# RasPi-BplusHAT.net
KiCad netlist of a schematic drawn in EAGLE
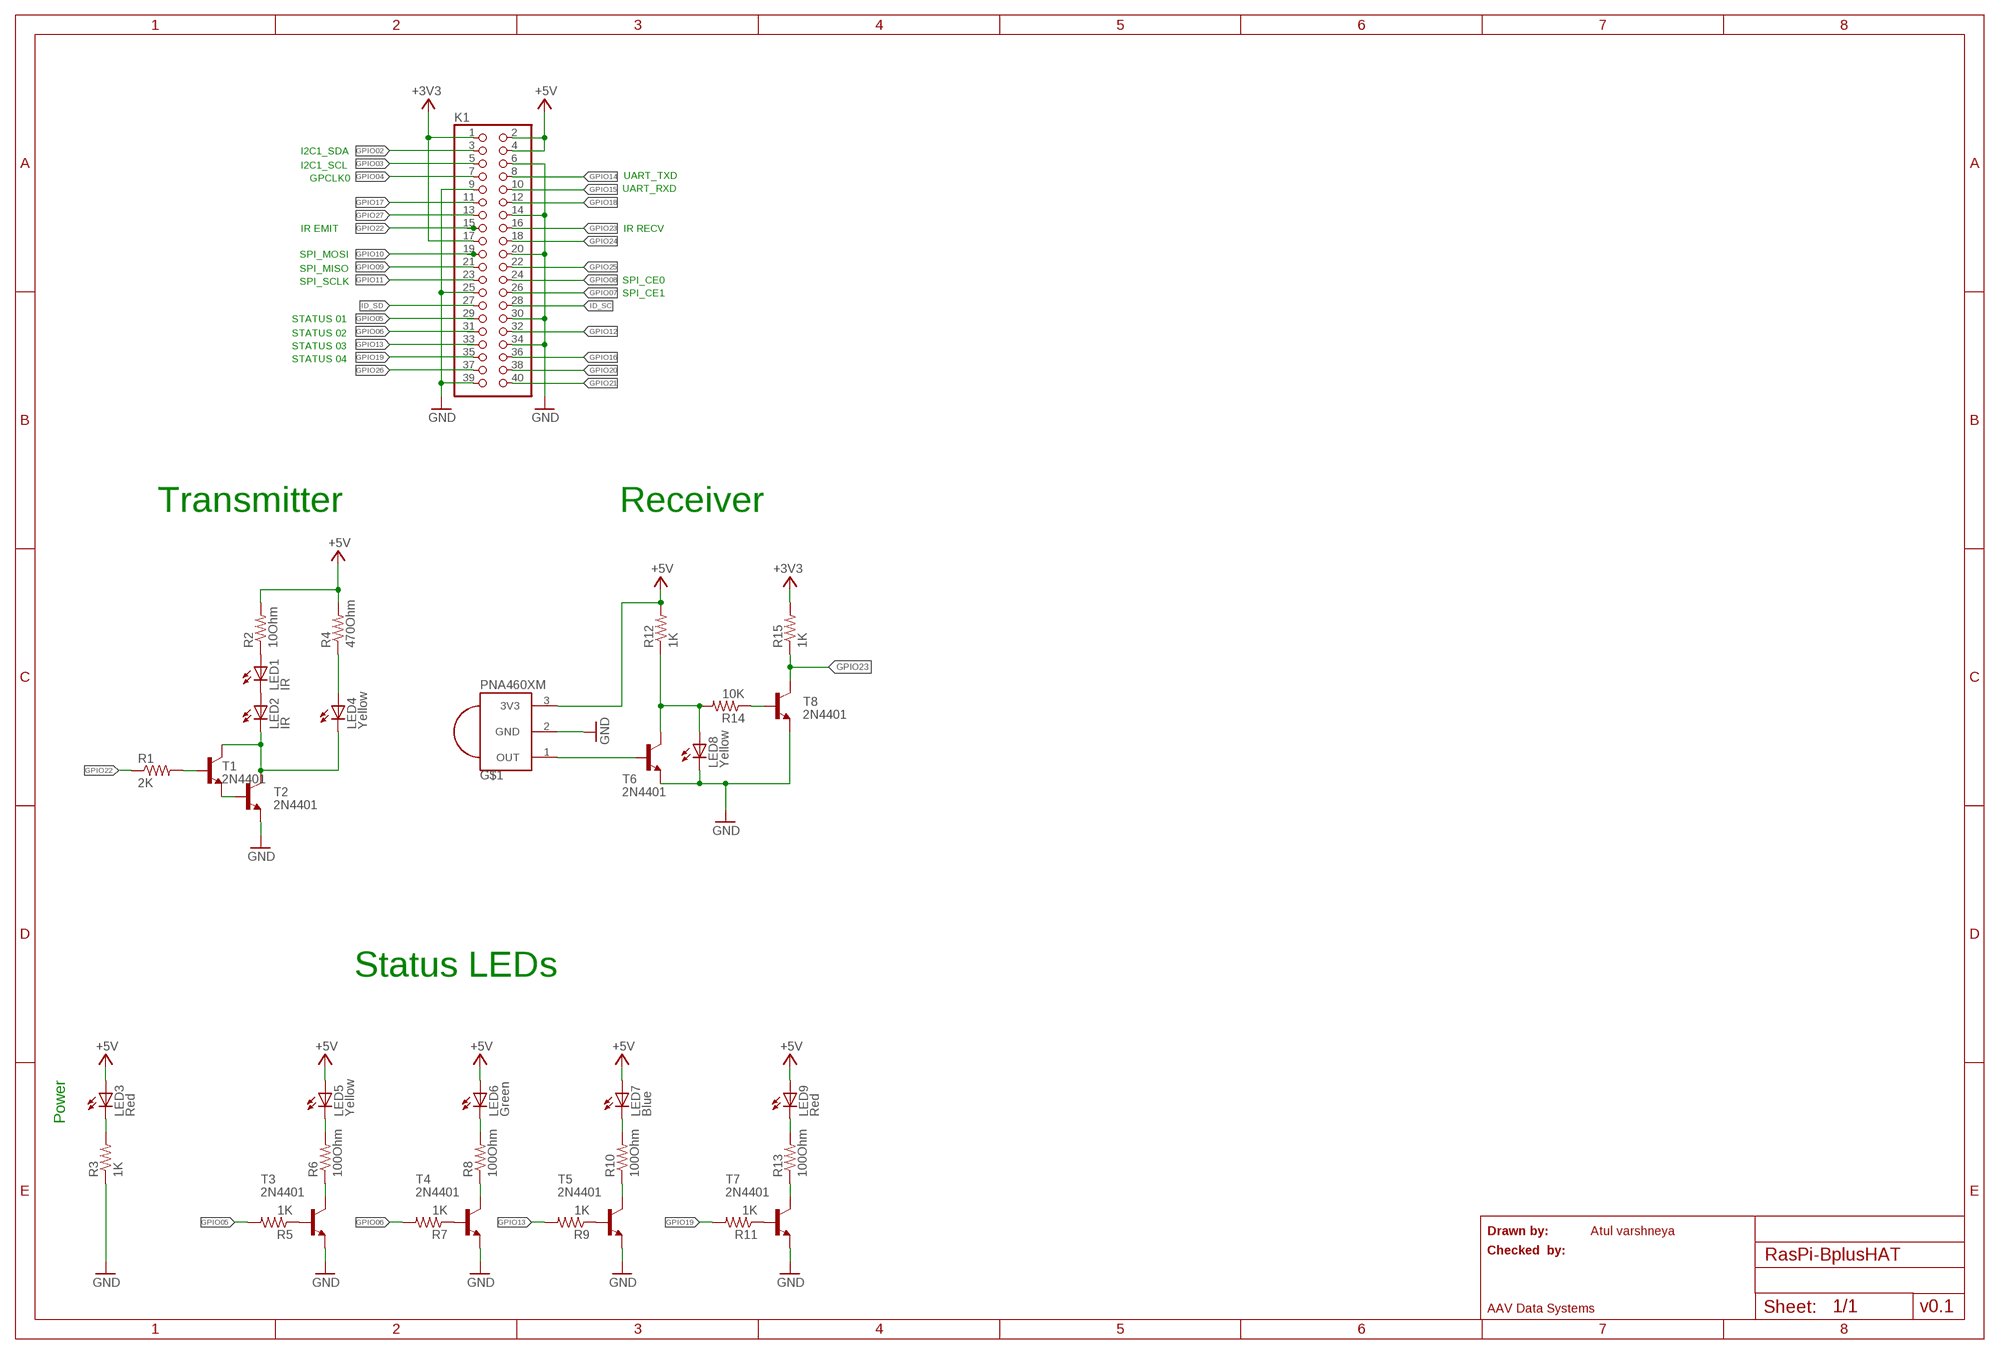
[diagram p0: schematic, sheet 1]

(export (version "E")
  (design (tool "Eeschema 10.0.6"))
  (components
    (comp (ref "G$1")
      (value "PNA460XM")
      (footprint "eagle-import:PNA460XM")
      (fields (field (name "MPN") "TSDP34138"))
      (libsource (lib "eagle-import") (part "PNA460XM"))
    )
    (comp (ref "K1")
      (value "PINHD-2X20")
      (footprint "eagle-import:2X20")
      (libsource (lib "eagle-import") (part "PINHD-2X20"))
    )
    (comp (ref "LED1")
      (value "IR")
      (footprint "eagle-import:MICRO-SIDELED")
      (fields (field (name "MPN") "VSMB10940X01"))
      (libsource (lib "eagle-import") (part "led_LEDMICRO-SIDELED"))
    )
    (comp (ref "LED2")
      (value "IR")
      (footprint "eagle-import:MICRO-SIDELED")
      (fields (field (name "MPN") "VSMB10940X01"))
      (libsource (lib "eagle-import") (part "led_LEDMICRO-SIDELED"))
    )
    (comp (ref "LED3")
      (value "Red")
      (footprint "eagle-import:CHIPLED_0805")
      (fields (field (name "MPN") "150080RS75000"))
      (libsource (lib "eagle-import") (part "LEDCHIPLED_0805"))
    )
    (comp (ref "LED4")
      (value "Yellow")
      (footprint "eagle-import:CHIPLED_0805")
      (fields (field (name "MPN") "150080YS75000"))
      (libsource (lib "eagle-import") (part "LEDCHIPLED_0805"))
    )
    (comp (ref "LED5")
      (value "Yellow")
      (footprint "eagle-import:CHIPLED_0805")
      (fields (field (name "MPN") "150080YS75000"))
      (libsource (lib "eagle-import") (part "LEDCHIPLED_0805"))
    )
    (comp (ref "LED6")
      (value "Green")
      (footprint "eagle-import:CHIPLED_0805")
      (fields (field (name "MPN") "150080GS75000"))
      (libsource (lib "eagle-import") (part "LEDCHIPLED_0805"))
    )
    (comp (ref "LED7")
      (value "Blue")
      (footprint "eagle-import:CHIPLED_0805")
      (fields (field (name "MPN") "150080BS75000"))
      (libsource (lib "eagle-import") (part "LEDCHIPLED_0805"))
    )
    (comp (ref "LED8")
      (value "Yellow")
      (footprint "eagle-import:CHIPLED_0805")
      (fields (field (name "MPN") "150080YS75000"))
      (libsource (lib "eagle-import") (part "LEDCHIPLED_0805"))
    )
    (comp (ref "LED9")
      (value "Red")
      (footprint "eagle-import:CHIPLED_0805")
      (fields (field (name "MPN") "150080RS75000"))
      (libsource (lib "eagle-import") (part "LEDCHIPLED_0805"))
    )
    (comp (ref "R1")
      (value "2K")
      (footprint "eagle-import:R0805")
      (fields (field (name "MPN") "CRCW08052K00JNEA"))
      (libsource (lib "eagle-import") (part "R-US_R0805"))
    )
    (comp (ref "R2")
      (value "10Ohm")
      (footprint "eagle-import:R0805")
      (fields (field (name "MF") "OUTSOURCE ITEM") (field (name "MPN") "RP2012S-100-F"))
      (libsource (lib "eagle-import") (part "R-US_R0805"))
    )
    (comp (ref "R3")
      (value "1K")
      (footprint "eagle-import:R0805")
      (fields (field (name "MF") "VISHAY/DALE") (field (name "MPN") "CRCW08051K00JNEA"))
      (libsource (lib "eagle-import") (part "rcl_R-US_R0805"))
    )
    (comp (ref "R4")
      (value "470Ohm")
      (footprint "eagle-import:R0805")
      (fields (field (name "MPN") "CRCW0805470RJNEA"))
      (libsource (lib "eagle-import") (part "R-US_R0805"))
    )
    (comp (ref "R5")
      (value "1K")
      (footprint "eagle-import:R0805")
      (fields (field (name "MF") "VISHAY/DALE") (field (name "MPN") "CRCW08051K00JNEA"))
      (libsource (lib "eagle-import") (part "rcl_R-US_R0805"))
    )
    (comp (ref "R6")
      (value "100Ohm")
      (footprint "eagle-import:R0805")
      (fields (field (name "MPN") "CRCW0805100RJNTA"))
      (libsource (lib "eagle-import") (part "rcl_R-US_R0805"))
    )
    (comp (ref "R7")
      (value "1K")
      (footprint "eagle-import:R0805")
      (fields (field (name "MF") "VISHAY/DALE") (field (name "MPN") "CRCW08051K00JNEA"))
      (libsource (lib "eagle-import") (part "rcl_R-US_R0805"))
    )
    (comp (ref "R8")
      (value "100Ohm")
      (footprint "eagle-import:R0805")
      (fields (field (name "MPN") "CRCW0805100RJNTA"))
      (libsource (lib "eagle-import") (part "rcl_R-US_R0805"))
    )
    (comp (ref "R9")
      (value "1K")
      (footprint "eagle-import:R0805")
      (fields (field (name "MF") "VISHAY/DALE") (field (name "MPN") "CRCW08051K00JNEA"))
      (libsource (lib "eagle-import") (part "rcl_R-US_R0805"))
    )
    (comp (ref "R10")
      (value "100Ohm")
      (footprint "eagle-import:R0805")
      (fields (field (name "MPN") "CRCW0805100RJNTA"))
      (libsource (lib "eagle-import") (part "rcl_R-US_R0805"))
    )
    (comp (ref "R11")
      (value "1K")
      (footprint "eagle-import:R0805")
      (fields (field (name "MF") "VISHAY/DALE") (field (name "MPN") "CRCW08051K00JNEA"))
      (libsource (lib "eagle-import") (part "rcl_R-US_R0805"))
    )
    (comp (ref "R12")
      (value "1K")
      (footprint "eagle-import:R0805")
      (fields (field (name "MF") "VISHAY/DALE") (field (name "MPN") "CRCW08051K00JNEA"))
      (libsource (lib "eagle-import") (part "rcl_R-US_R0805"))
    )
    (comp (ref "R13")
      (value "100Ohm")
      (footprint "eagle-import:R0805")
      (fields (field (name "MPN") "CRCW0805100RJNTA"))
      (libsource (lib "eagle-import") (part "rcl_R-US_R0805"))
    )
    (comp (ref "R14")
      (value "10K")
      (footprint "eagle-import:R0805")
      (fields (field (name "MF") "VISHAY/DALE") (field (name "MPN") "CRCW080510K0JNEB"))
      (libsource (lib "eagle-import") (part "rcl_R-US_R0805"))
    )
    (comp (ref "R15")
      (value "1K")
      (footprint "eagle-import:R0805")
      (fields (field (name "MF") "VISHAY/DALE") (field (name "MPN") "CRCW08051K00JNEA"))
      (libsource (lib "eagle-import") (part "rcl_R-US_R0805"))
    )
    (comp (ref "T1")
      (value "2N4401")
      (footprint "eagle-import:SOT23-BEC")
      (fields (field (name "MPN") "MMBT4401-TP"))
      (libsource (lib "eagle-import") (part "transistor-neu-to92_-NPN-SOT23-BECMMBT4401LT1"))
    )
    (comp (ref "T2")
      (value "2N4401")
      (footprint "eagle-import:SOT23-BEC")
      (fields (field (name "MPN") "MMBT4401-TP"))
      (libsource (lib "eagle-import") (part "transistor-neu-to92_-NPN-SOT23-BECMMBT4401LT1"))
    )
    (comp (ref "T3")
      (value "2N4401")
      (footprint "eagle-import:SOT23-BEC")
      (fields (field (name "MPN") "MMBT4401-TP"))
      (libsource (lib "eagle-import") (part "-NPN-SOT23-BECMMBT4401LT1"))
    )
    (comp (ref "T4")
      (value "2N4401")
      (footprint "eagle-import:SOT23-BEC")
      (fields (field (name "MPN") "MMBT4401-TP"))
      (libsource (lib "eagle-import") (part "-NPN-SOT23-BECMMBT4401LT1"))
    )
    (comp (ref "T5")
      (value "2N4401")
      (footprint "eagle-import:SOT23-BEC")
      (fields (field (name "MPN") "MMBT4401-TP"))
      (libsource (lib "eagle-import") (part "-NPN-SOT23-BECMMBT4401LT1"))
    )
    (comp (ref "T6")
      (value "2N4401")
      (footprint "eagle-import:SOT23-BEC")
      (fields (field (name "MPN") "MMBT4401-TP"))
      (libsource (lib "eagle-import") (part "-NPN-SOT23-BECMMBT4401LT1"))
    )
    (comp (ref "T7")
      (value "2N4401")
      (footprint "eagle-import:SOT23-BEC")
      (fields (field (name "MPN") "MMBT4401-TP"))
      (libsource (lib "eagle-import") (part "-NPN-SOT23-BECMMBT4401LT1"))
    )
    (comp (ref "T8")
      (value "2N4401")
      (footprint "eagle-import:SOT23-BEC")
      (fields (field (name "MPN") "MMBT4401-TP"))
      (libsource (lib "eagle-import") (part "-NPN-SOT23-BECMMBT4401LT1"))
    )
  )
  (nets
    (net (code "1") (name "+3V3") (class "Default")
      (node (ref "K1") (pin "1") (pinfunction "1_1") (pintype "passive"))
      (node (ref "K1") (pin "17") (pinfunction "17_17") (pintype "passive"))
      (node (ref "R15") (pin "2") (pinfunction "2_2") (pintype "passive"))
    )
    (net (code "2") (name "+5V") (class "Default")
      (node (ref "G$1") (pin "3") (pinfunction "3V3_3") (pintype "power_in"))
      (node (ref "K1") (pin "2") (pinfunction "2_2") (pintype "passive"))
      (node (ref "K1") (pin "4") (pinfunction "4_4") (pintype "passive"))
      (node (ref "LED3") (pin "A") (pinfunction "A_A") (pintype "passive"))
      (node (ref "LED5") (pin "A") (pinfunction "A_A") (pintype "passive"))
      (node (ref "LED6") (pin "A") (pinfunction "A_A") (pintype "passive"))
      (node (ref "LED7") (pin "A") (pinfunction "A_A") (pintype "passive"))
      (node (ref "LED9") (pin "A") (pinfunction "A_A") (pintype "passive"))
      (node (ref "R12") (pin "2") (pinfunction "2_2") (pintype "passive"))
      (node (ref "R2") (pin "2") (pinfunction "2_2") (pintype "passive"))
      (node (ref "R4") (pin "2") (pinfunction "2_2") (pintype "passive"))
    )
    (net (code "3") (name "GND") (class "Default")
      (node (ref "G$1") (pin "2") (pinfunction "GND_2") (pintype "power_in"))
      (node (ref "K1") (pin "14") (pinfunction "14_14") (pintype "passive"))
      (node (ref "K1") (pin "20") (pinfunction "20_20") (pintype "passive"))
      (node (ref "K1") (pin "25") (pinfunction "25_25") (pintype "passive"))
      (node (ref "K1") (pin "30") (pinfunction "30_30") (pintype "passive"))
      (node (ref "K1") (pin "34") (pinfunction "34_34") (pintype "passive"))
      (node (ref "K1") (pin "39") (pinfunction "39_39") (pintype "passive"))
      (node (ref "K1") (pin "6") (pinfunction "6_6") (pintype "passive"))
      (node (ref "K1") (pin "9") (pinfunction "9_9") (pintype "passive"))
      (node (ref "LED8") (pin "C") (pinfunction "C_C") (pintype "passive"))
      (node (ref "R3") (pin "1") (pinfunction "1_1") (pintype "passive"))
      (node (ref "T2") (pin "E") (pinfunction "E_E") (pintype "passive"))
      (node (ref "T3") (pin "E") (pinfunction "E_E") (pintype "passive"))
      (node (ref "T4") (pin "E") (pinfunction "E_E") (pintype "passive"))
      (node (ref "T5") (pin "E") (pinfunction "E_E") (pintype "passive"))
      (node (ref "T6") (pin "E") (pinfunction "E_E") (pintype "passive"))
      (node (ref "T7") (pin "E") (pinfunction "E_E") (pintype "passive"))
      (node (ref "T8") (pin "E") (pinfunction "E_E") (pintype "passive"))
    )
    (net (code "4") (name "GPIO02") (class "Default")
      (node (ref "K1") (pin "3") (pinfunction "3_3") (pintype "passive"))
    )
    (net (code "5") (name "GPIO03") (class "Default")
      (node (ref "K1") (pin "5") (pinfunction "5_5") (pintype "passive"))
    )
    (net (code "6") (name "GPIO04") (class "Default")
      (node (ref "K1") (pin "7") (pinfunction "7_7") (pintype "passive"))
    )
    (net (code "7") (name "GPIO05") (class "Default")
      (node (ref "K1") (pin "29") (pinfunction "29_29") (pintype "passive"))
      (node (ref "R5") (pin "2") (pinfunction "2_2") (pintype "passive"))
    )
    (net (code "8") (name "GPIO06") (class "Default")
      (node (ref "K1") (pin "31") (pinfunction "31_31") (pintype "passive"))
      (node (ref "R7") (pin "2") (pinfunction "2_2") (pintype "passive"))
    )
    (net (code "9") (name "GPIO07") (class "Default")
      (node (ref "K1") (pin "26") (pinfunction "26_26") (pintype "passive"))
    )
    (net (code "10") (name "GPIO08") (class "Default")
      (node (ref "K1") (pin "24") (pinfunction "24_24") (pintype "passive"))
    )
    (net (code "11") (name "GPIO09") (class "Default")
      (node (ref "K1") (pin "21") (pinfunction "21_21") (pintype "passive"))
    )
    (net (code "12") (name "GPIO10") (class "Default")
      (node (ref "K1") (pin "19") (pinfunction "19_19") (pintype "passive"))
    )
    (net (code "13") (name "GPIO11") (class "Default")
      (node (ref "K1") (pin "23") (pinfunction "23_23") (pintype "passive"))
    )
    (net (code "14") (name "GPIO12") (class "Default")
      (node (ref "K1") (pin "32") (pinfunction "32_32") (pintype "passive"))
    )
    (net (code "15") (name "GPIO13") (class "Default")
      (node (ref "K1") (pin "33") (pinfunction "33_33") (pintype "passive"))
      (node (ref "R9") (pin "2") (pinfunction "2_2") (pintype "passive"))
    )
    (net (code "16") (name "GPIO14") (class "Default")
      (node (ref "K1") (pin "8") (pinfunction "8_8") (pintype "passive"))
    )
    (net (code "17") (name "GPIO15") (class "Default")
      (node (ref "K1") (pin "10") (pinfunction "10_10") (pintype "passive"))
    )
    (net (code "18") (name "GPIO16") (class "Default")
      (node (ref "K1") (pin "36") (pinfunction "36_36") (pintype "passive"))
    )
    (net (code "19") (name "GPIO17") (class "Default")
      (node (ref "K1") (pin "11") (pinfunction "11_11") (pintype "passive"))
    )
    (net (code "20") (name "GPIO18") (class "Default")
      (node (ref "K1") (pin "12") (pinfunction "12_12") (pintype "passive"))
    )
    (net (code "21") (name "GPIO19") (class "Default")
      (node (ref "K1") (pin "35") (pinfunction "35_35") (pintype "passive"))
      (node (ref "R11") (pin "2") (pinfunction "2_2") (pintype "passive"))
    )
    (net (code "22") (name "GPIO20") (class "Default")
      (node (ref "K1") (pin "38") (pinfunction "38_38") (pintype "passive"))
    )
    (net (code "23") (name "GPIO21") (class "Default")
      (node (ref "K1") (pin "40") (pinfunction "40_40") (pintype "passive"))
    )
    (net (code "24") (name "GPIO22") (class "Default")
      (node (ref "K1") (pin "15") (pinfunction "15_15") (pintype "passive"))
      (node (ref "R1") (pin "1") (pinfunction "1_1") (pintype "passive"))
    )
    (net (code "25") (name "GPIO23") (class "Default")
      (node (ref "K1") (pin "16") (pinfunction "16_16") (pintype "passive"))
      (node (ref "R15") (pin "1") (pinfunction "1_1") (pintype "passive"))
      (node (ref "T8") (pin "C") (pinfunction "C_C") (pintype "passive"))
    )
    (net (code "26") (name "GPIO24") (class "Default")
      (node (ref "K1") (pin "18") (pinfunction "18_18") (pintype "passive"))
    )
    (net (code "27") (name "GPIO25") (class "Default")
      (node (ref "K1") (pin "22") (pinfunction "22_22") (pintype "passive"))
    )
    (net (code "28") (name "GPIO26") (class "Default")
      (node (ref "K1") (pin "37") (pinfunction "37_37") (pintype "passive"))
    )
    (net (code "29") (name "GPIO27") (class "Default")
      (node (ref "K1") (pin "13") (pinfunction "13_13") (pintype "passive"))
    )
    (net (code "30") (name "ID_SC") (class "Default")
      (node (ref "K1") (pin "28") (pinfunction "28_28") (pintype "passive"))
    )
    (net (code "31") (name "ID_SD") (class "Default")
      (node (ref "K1") (pin "27") (pinfunction "27_27") (pintype "passive"))
    )
    (net (code "32") (name "Net-(G$1-OUT)") (class "Default")
      (node (ref "G$1") (pin "1") (pinfunction "OUT_1") (pintype "output"))
      (node (ref "T6") (pin "B") (pinfunction "B_B") (pintype "passive"))
    )
    (net (code "33") (name "Net-(LED1-PadA)") (class "Default")
      (node (ref "LED1") (pin "A") (pinfunction "A_A") (pintype "passive"))
      (node (ref "R2") (pin "1") (pinfunction "1_1") (pintype "passive"))
    )
    (net (code "34") (name "Net-(LED1-PadC)") (class "Default")
      (node (ref "LED1") (pin "C") (pinfunction "C_C") (pintype "passive"))
      (node (ref "LED2") (pin "A") (pinfunction "A_A") (pintype "passive"))
    )
    (net (code "35") (name "Net-(LED2-PadC)") (class "Default")
      (node (ref "LED2") (pin "C") (pinfunction "C_C") (pintype "passive"))
      (node (ref "LED4") (pin "C") (pinfunction "C_C") (pintype "passive"))
      (node (ref "T1") (pin "C") (pinfunction "C_C") (pintype "passive"))
      (node (ref "T2") (pin "C") (pinfunction "C_C") (pintype "passive"))
    )
    (net (code "36") (name "Net-(LED3-PadC)") (class "Default")
      (node (ref "LED3") (pin "C") (pinfunction "C_C") (pintype "passive"))
      (node (ref "R3") (pin "2") (pinfunction "2_2") (pintype "passive"))
    )
    (net (code "37") (name "Net-(LED4-PadA)") (class "Default")
      (node (ref "LED4") (pin "A") (pinfunction "A_A") (pintype "passive"))
      (node (ref "R4") (pin "1") (pinfunction "1_1") (pintype "passive"))
    )
    (net (code "38") (name "Net-(LED5-PadC)") (class "Default")
      (node (ref "LED5") (pin "C") (pinfunction "C_C") (pintype "passive"))
      (node (ref "R6") (pin "2") (pinfunction "2_2") (pintype "passive"))
    )
    (net (code "39") (name "Net-(LED6-PadC)") (class "Default")
      (node (ref "LED6") (pin "C") (pinfunction "C_C") (pintype "passive"))
      (node (ref "R8") (pin "2") (pinfunction "2_2") (pintype "passive"))
    )
    (net (code "40") (name "Net-(LED7-PadC)") (class "Default")
      (node (ref "LED7") (pin "C") (pinfunction "C_C") (pintype "passive"))
      (node (ref "R10") (pin "2") (pinfunction "2_2") (pintype "passive"))
    )
    (net (code "41") (name "Net-(LED8-PadA)") (class "Default")
      (node (ref "LED8") (pin "A") (pinfunction "A_A") (pintype "passive"))
      (node (ref "R12") (pin "1") (pinfunction "1_1") (pintype "passive"))
      (node (ref "R14") (pin "2") (pinfunction "2_2") (pintype "passive"))
      (node (ref "T6") (pin "C") (pinfunction "C_C") (pintype "passive"))
    )
    (net (code "42") (name "Net-(LED9-PadC)") (class "Default")
      (node (ref "LED9") (pin "C") (pinfunction "C_C") (pintype "passive"))
      (node (ref "R13") (pin "2") (pinfunction "2_2") (pintype "passive"))
    )
    (net (code "43") (name "Net-(R1-Pad2)") (class "Default")
      (node (ref "R1") (pin "2") (pinfunction "2_2") (pintype "passive"))
      (node (ref "T1") (pin "B") (pinfunction "B_B") (pintype "passive"))
    )
    (net (code "44") (name "Net-(R5-Pad1)") (class "Default")
      (node (ref "R5") (pin "1") (pinfunction "1_1") (pintype "passive"))
      (node (ref "T3") (pin "B") (pinfunction "B_B") (pintype "passive"))
    )
    (net (code "45") (name "Net-(R6-Pad1)") (class "Default")
      (node (ref "R6") (pin "1") (pinfunction "1_1") (pintype "passive"))
      (node (ref "T3") (pin "C") (pinfunction "C_C") (pintype "passive"))
    )
    (net (code "46") (name "Net-(R7-Pad1)") (class "Default")
      (node (ref "R7") (pin "1") (pinfunction "1_1") (pintype "passive"))
      (node (ref "T4") (pin "B") (pinfunction "B_B") (pintype "passive"))
    )
    (net (code "47") (name "Net-(R8-Pad1)") (class "Default")
      (node (ref "R8") (pin "1") (pinfunction "1_1") (pintype "passive"))
      (node (ref "T4") (pin "C") (pinfunction "C_C") (pintype "passive"))
    )
    (net (code "48") (name "Net-(R9-Pad1)") (class "Default")
      (node (ref "R9") (pin "1") (pinfunction "1_1") (pintype "passive"))
      (node (ref "T5") (pin "B") (pinfunction "B_B") (pintype "passive"))
    )
    (net (code "49") (name "Net-(R10-Pad1)") (class "Default")
      (node (ref "R10") (pin "1") (pinfunction "1_1") (pintype "passive"))
      (node (ref "T5") (pin "C") (pinfunction "C_C") (pintype "passive"))
    )
    (net (code "50") (name "Net-(R11-Pad1)") (class "Default")
      (node (ref "R11") (pin "1") (pinfunction "1_1") (pintype "passive"))
      (node (ref "T7") (pin "B") (pinfunction "B_B") (pintype "passive"))
    )
    (net (code "51") (name "Net-(R13-Pad1)") (class "Default")
      (node (ref "R13") (pin "1") (pinfunction "1_1") (pintype "passive"))
      (node (ref "T7") (pin "C") (pinfunction "C_C") (pintype "passive"))
    )
    (net (code "52") (name "Net-(R14-Pad1)") (class "Default")
      (node (ref "R14") (pin "1") (pinfunction "1_1") (pintype "passive"))
      (node (ref "T8") (pin "B") (pinfunction "B_B") (pintype "passive"))
    )
    (net (code "53") (name "Net-(T1-PadE)") (class "Default")
      (node (ref "T1") (pin "E") (pinfunction "E_E") (pintype "passive"))
      (node (ref "T2") (pin "B") (pinfunction "B_B") (pintype "passive"))
    )
  )
)
